# RFD900module.net
KiCad netlist of a schematic drawn in EAGLE
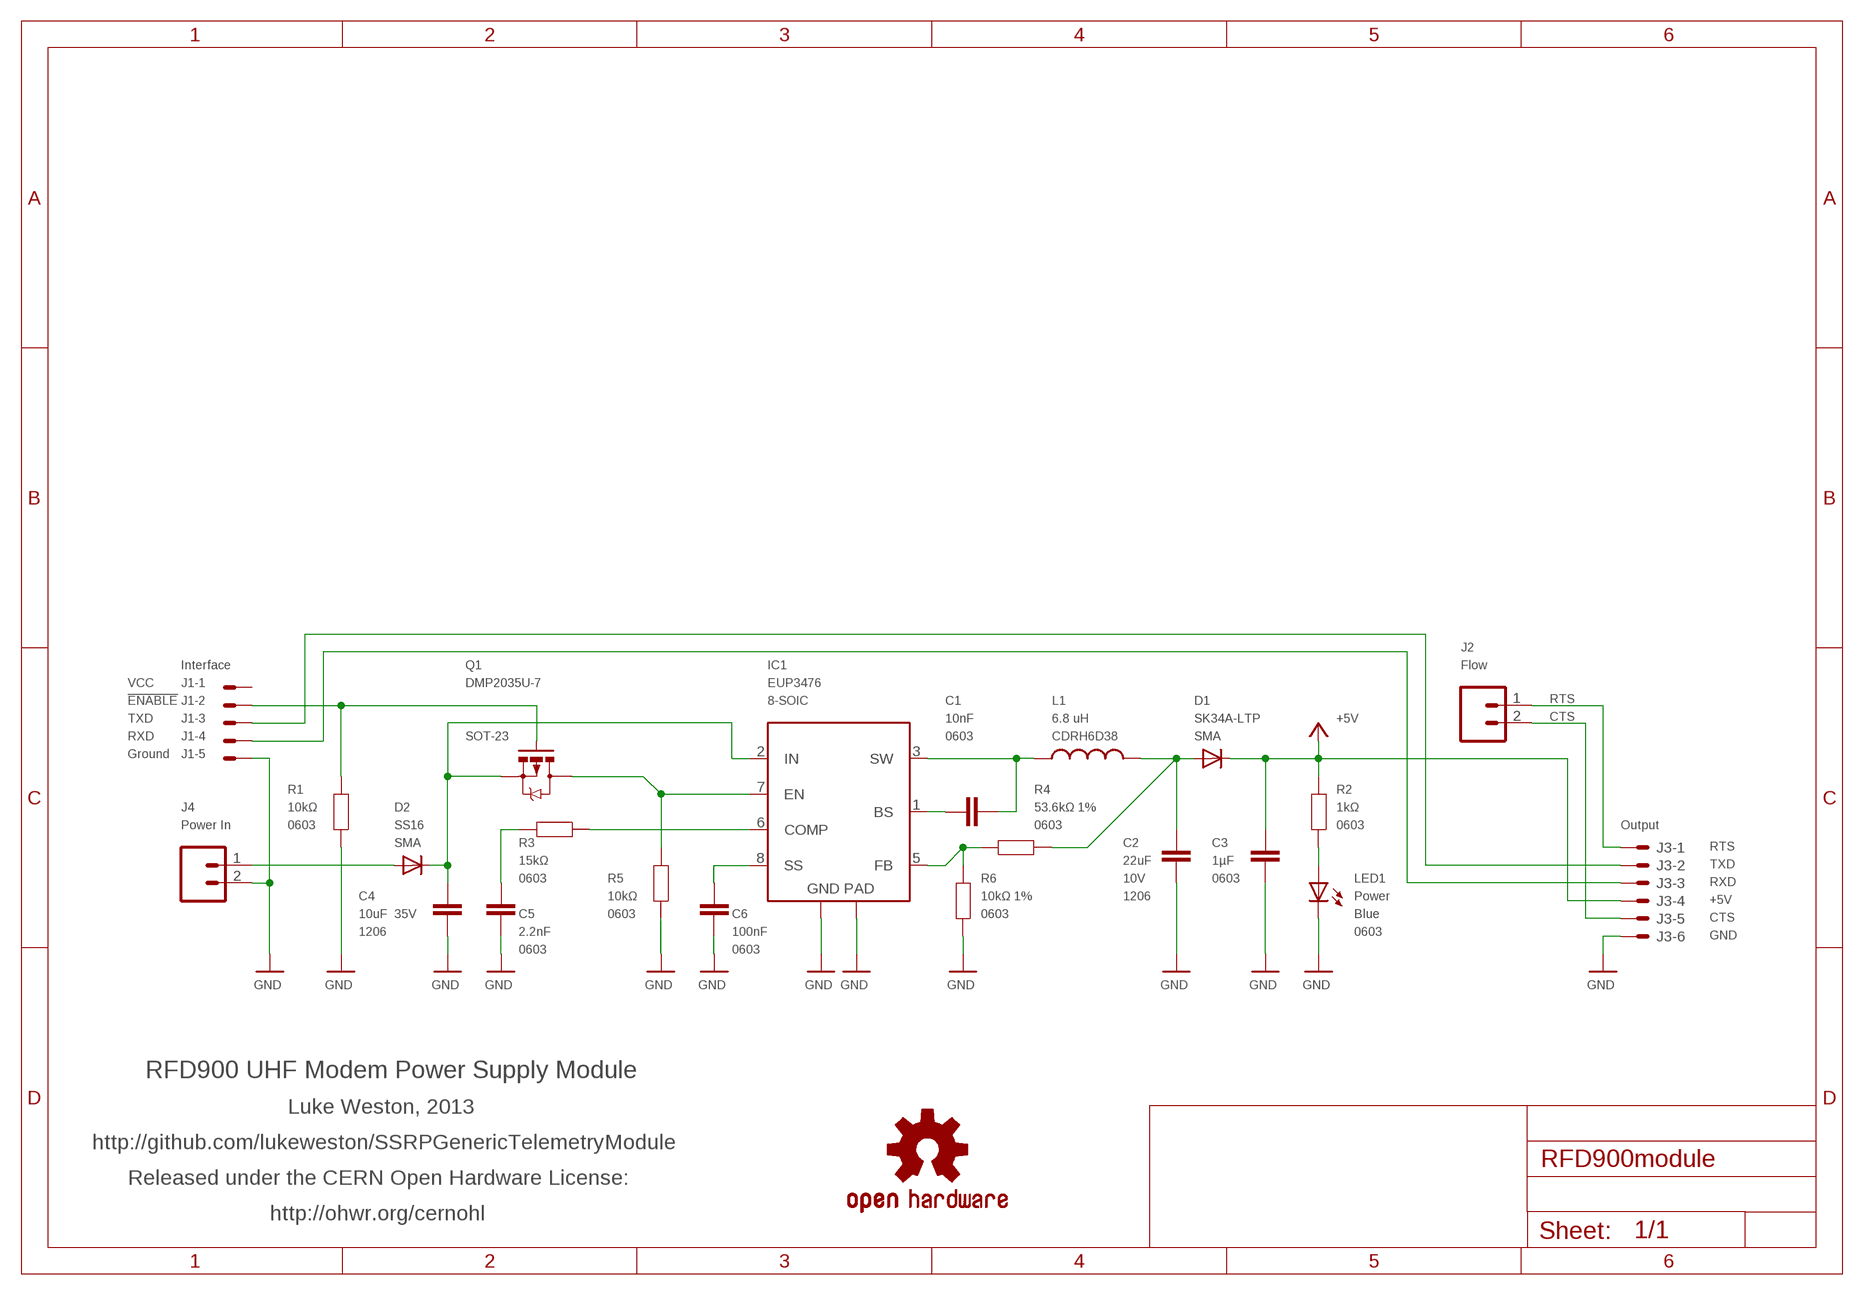
[diagram p0: schematic, sheet 1]

(export (version "E")
  (design (tool "Eeschema 10.0.6"))
  (components
    (comp (ref "C1")
      (value "10nF")
      (footprint "eagle-import:0603")
      (fields (field (name "PACKAGE") "0603"))
      (libsource (lib "eagle-import") (part "CAP0603"))
    )
    (comp (ref "C2")
      (value "22uF")
      (footprint "eagle-import:C1206")
      (fields (field (name "PACKAGE") "1206") (field (name "VOLTAGE") "10V"))
      (libsource (lib "eagle-import") (part "C-EUC1206"))
    )
    (comp (ref "C3")
      (value "1µF")
      (footprint "eagle-import:0603")
      (fields (field (name "PACKAGE") "0603"))
      (libsource (lib "eagle-import") (part "CAP0603"))
    )
    (comp (ref "C4")
      (value "10uF")
      (footprint "eagle-import:C1206")
      (fields (field (name "PACKAGE") "1206") (field (name "VOLTAGE") "35V"))
      (libsource (lib "eagle-import") (part "C-EUC1206"))
    )
    (comp (ref "C5")
      (value "2.2nF")
      (footprint "eagle-import:0603")
      (fields (field (name "PACKAGE") "0603"))
      (libsource (lib "eagle-import") (part "CAP0603"))
    )
    (comp (ref "C6")
      (value "100nF")
      (footprint "eagle-import:0603")
      (fields (field (name "PACKAGE") "0603"))
      (libsource (lib "eagle-import") (part "CAP0603"))
    )
    (comp (ref "D1")
      (value "SK34A-LTP")
      (footprint "eagle-import:SMA-DIODE")
      (fields (field (name "PACKAGE") "SMA"))
      (libsource (lib "eagle-import") (part "freetronics-master-v1_DIODESMA"))
    )
    (comp (ref "D2")
      (value "SS16")
      (footprint "eagle-import:SMA-SMB-DIODE")
      (fields (field (name "PACKAGE") "SMA"))
      (libsource (lib "eagle-import") (part "DIODESMAB"))
    )
    (comp (ref "IC1")
      (value "EUP3476")
      (footprint "eagle-import:SO08T")
      (fields (field (name "PACKAGE") "8-SOIC"))
      (libsource (lib "eagle-import") (part "EUP3476"))
    )
    (comp (ref "J1")
      (value "Interface")
      (footprint "eagle-import:22-23-2051")
      (fields (field (name "MF") "MOLEX") (field (name "MPN") "22-23-2051"))
      (libsource (lib "eagle-import") (part "22-23-2051"))
    )
    (comp (ref "J2")
      (value "Flow")
      (footprint "eagle-import:1X02")
      (libsource (lib "eagle-import") (part "M02PTH"))
    )
    (comp (ref "J3")
      (value "Output")
      (footprint "eagle-import:22-23-2061")
      (fields (field (name "MF") "MOLEX") (field (name "MPN") "22-23-2061"))
      (libsource (lib "eagle-import") (part "22-23-2061"))
    )
    (comp (ref "J4")
      (value "Power In")
      (footprint "eagle-import:SCREWTERMINAL-3.5MM-2")
      (libsource (lib "eagle-import") (part "M023.5MM"))
    )
    (comp (ref "L1")
      (value "6.8 uH")
      (footprint "eagle-import:CDRH")
      (fields (field (name "SKU") "CDRH6D38"))
      (libsource (lib "eagle-import") (part "INDUCTOR"))
    )
    (comp (ref "LED1")
      (value "Power")
      (footprint "eagle-import:LED-0603")
      (fields (field (name "COLOUR") "Blue") (field (name "PACKAGE") "0603"))
      (libsource (lib "eagle-import") (part "LED0603"))
    )
    (comp (ref "Q1")
      (value "DMP2035U-7")
      (footprint "eagle-import:SOT23-3")
      (fields (field (name "PACKAGE") "SOT-23"))
      (libsource (lib "eagle-import") (part "DMP2035U-7"))
    )
    (comp (ref "R1")
      (value "10kΩ")
      (footprint "eagle-import:0603")
      (fields (field (name "PACKAGE") "0603"))
      (libsource (lib "eagle-import") (part "RESISTOR0603"))
    )
    (comp (ref "R2")
      (value "1kΩ")
      (footprint "eagle-import:0603")
      (fields (field (name "PACKAGE") "0603"))
      (libsource (lib "eagle-import") (part "RESISTOR0603"))
    )
    (comp (ref "R3")
      (value "15kΩ")
      (footprint "eagle-import:0603")
      (fields (field (name "PACKAGE") "0603"))
      (libsource (lib "eagle-import") (part "RESISTOR0603"))
    )
    (comp (ref "R4")
      (value "53.6kΩ 1%")
      (footprint "eagle-import:0603")
      (fields (field (name "PACKAGE") "0603"))
      (libsource (lib "eagle-import") (part "RESISTOR0603"))
    )
    (comp (ref "R5")
      (value "10kΩ")
      (footprint "eagle-import:0603")
      (fields (field (name "PACKAGE") "0603"))
      (libsource (lib "eagle-import") (part "RESISTOR0603"))
    )
    (comp (ref "R6")
      (value "10kΩ 1%")
      (footprint "eagle-import:0603")
      (fields (field (name "PACKAGE") "0603"))
      (libsource (lib "eagle-import") (part "RESISTOR0603"))
    )
    (comp (ref "SY")
      (value "OSHW-LOGOS")
      (footprint "eagle-import:OSHW-LOGO-S")
      (libsource (lib "eagle-import") (part "OSHW-LOGOS"))
    )
  )
  (nets
    (net (code "1") (name "+5V") (class "Default")
      (node (ref "C3") (pin "2") (pinfunction "2_2") (pintype "passive"))
      (node (ref "D1") (pin "C") (pinfunction "C_C") (pintype "passive"))
      (node (ref "J3") (pin "4") (pinfunction "S_4") (pintype "passive"))
      (node (ref "R2") (pin "1") (pinfunction "1_1") (pintype "passive"))
    )
    (net (code "2") (name "/CTS") (class "Default")
      (node (ref "J2") (pin "2") (pinfunction "2_2") (pintype "passive"))
      (node (ref "J3") (pin "5") (pinfunction "S_5") (pintype "passive"))
    )
    (net (code "3") (name "/RTS") (class "Default")
      (node (ref "J2") (pin "1") (pinfunction "1_1") (pintype "passive"))
      (node (ref "J3") (pin "1") (pinfunction "S_1") (pintype "passive"))
    )
    (net (code "4") (name "GND") (class "Default")
      (node (ref "C2") (pin "2") (pinfunction "2_2") (pintype "passive"))
      (node (ref "C3") (pin "1") (pinfunction "1_1") (pintype "passive"))
      (node (ref "C4") (pin "2") (pinfunction "2_2") (pintype "passive"))
      (node (ref "C5") (pin "1") (pinfunction "1_1") (pintype "passive"))
      (node (ref "C6") (pin "1") (pinfunction "1_1") (pintype "passive"))
      (node (ref "IC1") (pin "4") (pinfunction "GND_4") (pintype "power_in"))
      (node (ref "IC1") (pin "9") (pinfunction "TGND_9") (pintype "power_in"))
      (node (ref "J1") (pin "5") (pinfunction "S_5") (pintype "passive"))
      (node (ref "J3") (pin "6") (pinfunction "S_6") (pintype "passive"))
      (node (ref "J4") (pin "2") (pinfunction "2_2") (pintype "passive"))
      (node (ref "LED1") (pin "C") (pinfunction "C_C") (pintype "passive"))
      (node (ref "R1") (pin "2") (pinfunction "2_2") (pintype "passive"))
      (node (ref "R5") (pin "2") (pinfunction "2_2") (pintype "passive"))
      (node (ref "R6") (pin "2") (pinfunction "2_2") (pintype "passive"))
    )
    (net (code "5") (name "Net-(C2-Pad1)") (class "Default")
      (node (ref "C2") (pin "1") (pinfunction "1_1") (pintype "passive"))
      (node (ref "D1") (pin "A") (pinfunction "A_A") (pintype "passive"))
      (node (ref "L1") (pin "2") (pinfunction "2_2") (pintype "bidirectional"))
      (node (ref "R4") (pin "2") (pinfunction "2_2") (pintype "passive"))
    )
    (net (code "6") (name "Net-(C5-Pad2)") (class "Default")
      (node (ref "C5") (pin "2") (pinfunction "2_2") (pintype "passive"))
      (node (ref "R3") (pin "2") (pinfunction "2_2") (pintype "passive"))
    )
    (net (code "7") (name "Net-(D2-PadA)") (class "Default")
      (node (ref "D2") (pin "A") (pinfunction "A_A") (pintype "passive"))
      (node (ref "J4") (pin "1") (pinfunction "1_1") (pintype "passive"))
    )
    (net (code "8") (name "Net-(IC1-BS)") (class "Default")
      (node (ref "C1") (pin "2") (pinfunction "2_2") (pintype "passive"))
      (node (ref "IC1") (pin "1") (pinfunction "BS_1") (pintype "bidirectional"))
    )
    (net (code "9") (name "Net-(IC1-COMP)") (class "Default")
      (node (ref "IC1") (pin "6") (pinfunction "COMP_6") (pintype "bidirectional"))
      (node (ref "R3") (pin "1") (pinfunction "1_1") (pintype "passive"))
    )
    (net (code "10") (name "Net-(IC1-EN)") (class "Default")
      (node (ref "IC1") (pin "7") (pinfunction "EN_7") (pintype "input"))
      (node (ref "Q1") (pin "3") (pinfunction "D_3") (pintype "passive"))
      (node (ref "R5") (pin "1") (pinfunction "1_1") (pintype "passive"))
    )
    (net (code "11") (name "Net-(IC1-FB)") (class "Default")
      (node (ref "IC1") (pin "5") (pinfunction "FB_5") (pintype "bidirectional"))
      (node (ref "R4") (pin "1") (pinfunction "1_1") (pintype "passive"))
      (node (ref "R6") (pin "1") (pinfunction "1_1") (pintype "passive"))
    )
    (net (code "12") (name "Net-(IC1-IN)") (class "Default")
      (node (ref "C4") (pin "1") (pinfunction "1_1") (pintype "passive"))
      (node (ref "D2") (pin "C") (pinfunction "C_C") (pintype "passive"))
      (node (ref "IC1") (pin "2") (pinfunction "IN_2") (pintype "power_in"))
      (node (ref "Q1") (pin "2") (pinfunction "S_2") (pintype "passive"))
    )
    (net (code "13") (name "Net-(IC1-SS)") (class "Default")
      (node (ref "C6") (pin "2") (pinfunction "2_2") (pintype "passive"))
      (node (ref "IC1") (pin "8") (pinfunction "SS_8") (pintype "bidirectional"))
    )
    (net (code "14") (name "Net-(IC1-SW)") (class "Default")
      (node (ref "C1") (pin "1") (pinfunction "1_1") (pintype "passive"))
      (node (ref "IC1") (pin "3") (pinfunction "SW_3") (pintype "bidirectional"))
      (node (ref "L1") (pin "1") (pinfunction "1_1") (pintype "bidirectional"))
    )
    (net (code "15") (name "Net-(J1B-S)") (class "Default")
      (node (ref "J1") (pin "2") (pinfunction "S_2") (pintype "passive"))
      (node (ref "Q1") (pin "1") (pinfunction "G_1") (pintype "passive"))
      (node (ref "R1") (pin "1") (pinfunction "1_1") (pintype "passive"))
    )
    (net (code "16") (name "Net-(J1C-S)") (class "Default")
      (node (ref "J1") (pin "3") (pinfunction "S_3") (pintype "passive"))
      (node (ref "J3") (pin "2") (pinfunction "S_2") (pintype "passive"))
    )
    (net (code "17") (name "Net-(J1D-S)") (class "Default")
      (node (ref "J1") (pin "4") (pinfunction "S_4") (pintype "passive"))
      (node (ref "J3") (pin "3") (pinfunction "S_3") (pintype "passive"))
    )
    (net (code "18") (name "Net-(LED1-PadA)") (class "Default")
      (node (ref "LED1") (pin "A") (pinfunction "A_A") (pintype "passive"))
      (node (ref "R2") (pin "2") (pinfunction "2_2") (pintype "passive"))
    )
    (net (code "19") (name "unconnected-(J1A-S-Pad1)") (class "Default")
      (node (ref "J1") (pin "1") (pinfunction "S_1") (pintype "passive"))
    )
  )
)
